# scale-slave.net
KiCad netlist of a schematic drawn in EAGLE
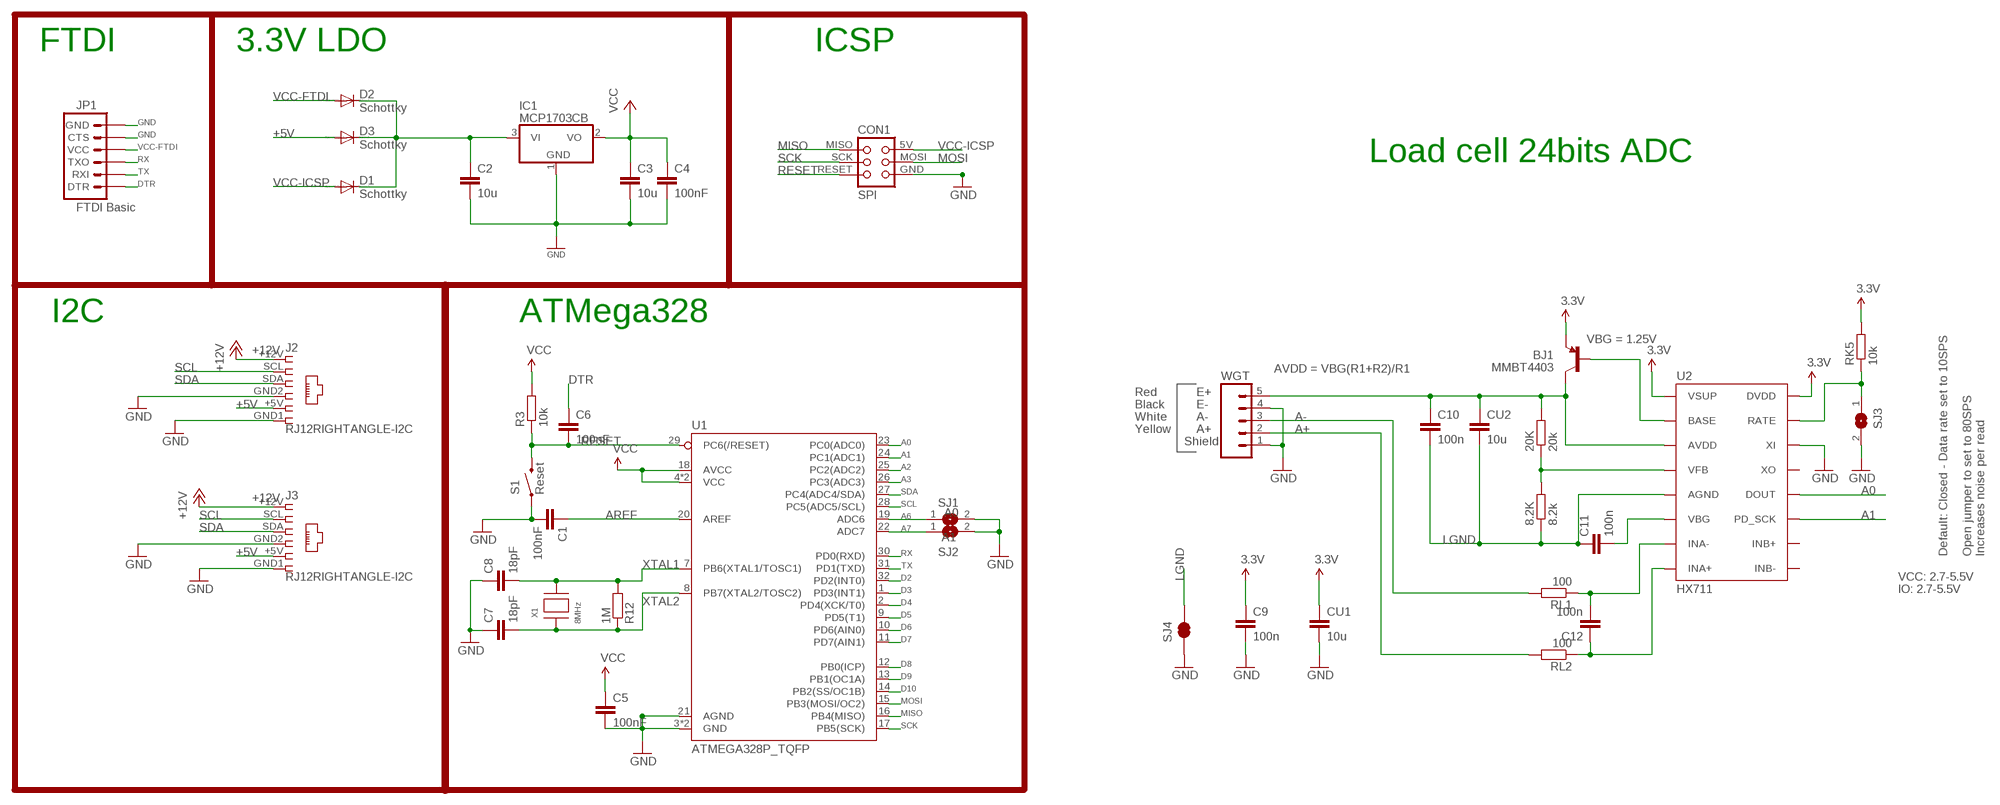
[diagram p0: schematic, sheet 1]

(export (version "E")
  (design (tool "Eeschema 10.0.6"))
  (components
    (comp (ref "8.2K")
      (value "8.2k")
      (footprint "eagle-import:M0805")
      (libsource (lib "eagle-import") (part "resistor_R-EU_M0805"))
    )
    (comp (ref "20K")
      (value "20k")
      (footprint "eagle-import:M0805")
      (libsource (lib "eagle-import") (part "resistor_R-EU_M0805"))
    )
    (comp (ref "BJ1")
      (value "MMBT4403")
      (footprint "eagle-import:SOT23-3")
      (libsource (lib "eagle-import") (part "TRANSISTOR_PNPMMBT4403"))
    )
    (comp (ref "C1")
      (value "100nF")
      (footprint "eagle-import:C0805K")
      (fields (field (name "MPN") "80-C1206C104K5R"))
      (libsource (lib "eagle-import") (part "rcl_334_C-EUC0805K"))
    )
    (comp (ref "C2")
      (value "10u")
      (footprint "eagle-import:C0805K")
      (fields (field (name "MPN") "77-VJ1206V106ZXQTBC"))
      (libsource (lib "eagle-import") (part "rcl_334_C-EUC0805K"))
    )
    (comp (ref "C3")
      (value "10u")
      (footprint "eagle-import:C0805K")
      (fields (field (name "MPN") "77-VJ1206V106ZXQTBC"))
      (libsource (lib "eagle-import") (part "rcl_334_C-EUC0805K"))
    )
    (comp (ref "C4")
      (value "100nF")
      (footprint "eagle-import:C0805K")
      (fields (field (name "MPN") "80-C1206C104K5R"))
      (libsource (lib "eagle-import") (part "rcl_334_C-EUC0805K"))
    )
    (comp (ref "C5")
      (value "100nF")
      (footprint "eagle-import:C0805K")
      (fields (field (name "MPN") "80-C1206C104K5R"))
      (libsource (lib "eagle-import") (part "rcl_334_C-EUC0805K"))
    )
    (comp (ref "C6")
      (value "100nF")
      (footprint "eagle-import:C0805K")
      (fields (field (name "MPN") "80-C1206C104K5R"))
      (libsource (lib "eagle-import") (part "rcl_334_C-EUC0805K"))
    )
    (comp (ref "C7")
      (value "18pF")
      (footprint "eagle-import:C0805K")
      (fields (field (name "MPN") "77-VJ1206A180JXXPBC"))
      (libsource (lib "eagle-import") (part "rcl_334_C-EUC0805K"))
    )
    (comp (ref "C8")
      (value "18pF")
      (footprint "eagle-import:C0805K")
      (fields (field (name "MPN") "77-VJ1206A180JXXPBC"))
      (libsource (lib "eagle-import") (part "rcl_334_C-EUC0805K"))
    )
    (comp (ref "C9")
      (value "100n")
      (footprint "eagle-import:C0805")
      (libsource (lib "eagle-import") (part "C-EUC0805"))
    )
    (comp (ref "C10")
      (value "100n")
      (footprint "eagle-import:C0805")
      (libsource (lib "eagle-import") (part "C-EUC0805"))
    )
    (comp (ref "C11")
      (value "100n")
      (footprint "eagle-import:C0805")
      (libsource (lib "eagle-import") (part "C-EUC0805"))
    )
    (comp (ref "C12")
      (value "100n")
      (footprint "eagle-import:C0805")
      (libsource (lib "eagle-import") (part "C-EUC0805"))
    )
    (comp (ref "CON1")
      (value "SPI")
      (footprint "eagle-import:TC2030-MCP")
      (libsource (lib "eagle-import") (part "TINYISPTAG"))
    )
    (comp (ref "CU1")
      (value "10u")
      (footprint "eagle-import:C0805")
      (libsource (lib "eagle-import") (part "C-EUC0805"))
    )
    (comp (ref "CU2")
      (value "10u")
      (footprint "eagle-import:C0805")
      (libsource (lib "eagle-import") (part "C-EUC0805"))
    )
    (comp (ref "D1")
      (value "Schottky")
      (footprint "eagle-import:SOD123")
      (fields (field (name "MPN") "621-1N5819HW-F"))
      (libsource (lib "eagle-import") (part "MBR0520LT"))
    )
    (comp (ref "D2")
      (value "Schottky")
      (footprint "eagle-import:SOD123")
      (fields (field (name "MPN") "621-1N5819HW-F"))
      (libsource (lib "eagle-import") (part "MBR0520LT"))
    )
    (comp (ref "D3")
      (value "Schottky")
      (footprint "eagle-import:SOD123")
      (fields (field (name "MPN") "621-1N5819HW-F"))
      (libsource (lib "eagle-import") (part "MBR0520LT"))
    )
    (comp (ref "IC1")
      (value "MCP1703CB")
      (footprint "eagle-import:SOT23")
      (libsource (lib "eagle-import") (part "MCP1703CB"))
    )
    (comp (ref "J2")
      (value "RJ12RIGHTANGLE-I2C")
      (footprint "eagle-import:RJ12-RIGHTANGLE-I2C")
      (libsource (lib "eagle-import") (part "RJ12RIGHTANGLE-I2C"))
    )
    (comp (ref "J3")
      (value "RJ12RIGHTANGLE-I2C")
      (footprint "eagle-import:RJ12-RIGHTANGLE-I2C")
      (libsource (lib "eagle-import") (part "RJ12RIGHTANGLE-I2C"))
    )
    (comp (ref "JP1")
      (value "FTDI Basic")
      (footprint "eagle-import:1X06")
      (libsource (lib "eagle-import") (part "ARDUINO_SERIAL_PROGRAMPTH"))
    )
    (comp (ref "R3")
      (value "10k")
      (footprint "eagle-import:R0805")
      (libsource (lib "eagle-import") (part "R-EU_R0805"))
    )
    (comp (ref "R12")
      (value "1M")
      (footprint "eagle-import:R0805")
      (libsource (lib "eagle-import") (part "R-EU_R0805"))
    )
    (comp (ref "RK5")
      (value "10k")
      (footprint "eagle-import:M0805")
      (libsource (lib "eagle-import") (part "resistor_R-EU_M0805"))
    )
    (comp (ref "RL1")
      (value "100")
      (footprint "eagle-import:M0805")
      (libsource (lib "eagle-import") (part "resistor_R-EU_M0805"))
    )
    (comp (ref "RL2")
      (value "100")
      (footprint "eagle-import:M0805")
      (libsource (lib "eagle-import") (part "resistor_R-EU_M0805"))
    )
    (comp (ref "S1")
      (value "Reset")
      (footprint "eagle-import:TACTILE-SWITCH-SMD-ALT01")
      (libsource (lib "eagle-import") (part "SWITCH-MOMENTARY-2SMD-ALT01"))
    )
    (comp (ref "SJ1")
      (value "A0")
      (footprint "eagle-import:SJ")
      (libsource (lib "eagle-import") (part "jumper_252_SJ"))
    )
    (comp (ref "SJ2")
      (value "A1")
      (footprint "eagle-import:SJ")
      (libsource (lib "eagle-import") (part "jumper_252_SJ"))
    )
    (comp (ref "SJ3") (value "SJ") (footprint "eagle-import:SJ") (libsource (lib "eagle-import") (part "SJ")))
    (comp (ref "SJ4")
      (value "JUMPER-PAD-2-NC_BY_TRACE")
      (footprint "eagle-import:PAD-JUMPER-2-NC_BY_TRACE_YES_SILK")
      (libsource (lib "eagle-import") (part "JUMPER-PAD-2-NC_BY_TRACE"))
    )
    (comp (ref "U1")
      (value "ATMEGA328P_TQFP")
      (footprint "eagle-import:TQFP32-08")
      (libsource (lib "eagle-import") (part "ATMEGA328P_TQFP"))
    )
    (comp (ref "U2")
      (value "HX711")
      (footprint "eagle-import:SO16")
      (libsource (lib "eagle-import") (part "HX711HX711"))
    )
    (comp (ref "WGT")
      (value "M05PTH")
      (footprint "eagle-import:1X05")
      (libsource (lib "eagle-import") (part "M05PTH"))
    )
    (comp (ref "X1")
      (value "8MHz")
      (footprint "eagle-import:NX6035")
      (fields (field (name "MPN") "729-F60800010"))
      (libsource (lib "eagle-import") (part "XTALNX6035"))
    )
  )
  (nets
    (net (code "1") (name "+12V") (class "Default")
      (node (ref "J2") (pin "+12V") (pinfunction "1_+12V") (pintype "bidirectional"))
      (node (ref "J3") (pin "+12V") (pinfunction "1_+12V") (pintype "bidirectional"))
    )
    (net (code "2") (name "/+5V") (class "Default")
      (node (ref "D3") (pin "A") (pinfunction "A_A") (pintype "passive"))
      (node (ref "J2") (pin "+5V") (pinfunction "5_+5V") (pintype "bidirectional"))
      (node (ref "J3") (pin "+5V") (pinfunction "5_+5V") (pintype "bidirectional"))
    )
    (net (code "3") (name "/A+") (class "Default")
      (node (ref "RL2") (pin "2") (pinfunction "2_2") (pintype "passive"))
      (node (ref "WGT") (pin "2") (pinfunction "2_2") (pintype "passive"))
    )
    (net (code "4") (name "/A-") (class "Default")
      (node (ref "RL1") (pin "2") (pinfunction "2_2") (pintype "passive"))
      (node (ref "WGT") (pin "3") (pinfunction "3_3") (pintype "passive"))
    )
    (net (code "5") (name "/A0") (class "Default")
      (node (ref "U1") (pin "23") (pinfunction "PC0(ADC0)_23") (pintype "bidirectional"))
      (node (ref "U2") (pin "12") (pinfunction "DOUT_12") (pintype "bidirectional"))
    )
    (net (code "6") (name "/A1") (class "Default")
      (node (ref "U1") (pin "24") (pinfunction "PC1(ADC1)_24") (pintype "bidirectional"))
      (node (ref "U2") (pin "11") (pinfunction "PD_SCK_11") (pintype "bidirectional"))
    )
    (net (code "7") (name "/A2") (class "Default")
      (node (ref "U1") (pin "25") (pinfunction "PC2(ADC2)_25") (pintype "bidirectional"))
    )
    (net (code "8") (name "/A3") (class "Default")
      (node (ref "U1") (pin "26") (pinfunction "PC3(ADC3)_26") (pintype "bidirectional"))
    )
    (net (code "9") (name "/A6") (class "Default")
      (node (ref "SJ1") (pin "1") (pinfunction "1_1") (pintype "passive"))
      (node (ref "U1") (pin "19") (pinfunction "ADC6_19") (pintype "bidirectional"))
    )
    (net (code "10") (name "/A7") (class "Default")
      (node (ref "SJ2") (pin "1") (pinfunction "1_1") (pintype "passive"))
      (node (ref "U1") (pin "22") (pinfunction "ADC7_22") (pintype "bidirectional"))
    )
    (net (code "11") (name "/AREF") (class "Default")
      (node (ref "C1") (pin "1") (pinfunction "1_1") (pintype "passive"))
      (node (ref "U1") (pin "20") (pinfunction "AREF_20") (pintype "bidirectional"))
    )
    (net (code "12") (name "/D2") (class "Default")
      (node (ref "U1") (pin "32") (pinfunction "PD2(INT0)_32") (pintype "bidirectional"))
    )
    (net (code "13") (name "/D3") (class "Default")
      (node (ref "U1") (pin "1") (pinfunction "PD3(INT1)_1") (pintype "bidirectional"))
    )
    (net (code "14") (name "/D4") (class "Default")
      (node (ref "U1") (pin "2") (pinfunction "PD4(XCK/T0)_2") (pintype "bidirectional"))
    )
    (net (code "15") (name "/D5") (class "Default")
      (node (ref "U1") (pin "9") (pinfunction "PD5(T1)_9") (pintype "bidirectional"))
    )
    (net (code "16") (name "/D6") (class "Default")
      (node (ref "U1") (pin "10") (pinfunction "PD6(AIN0)_10") (pintype "bidirectional"))
    )
    (net (code "17") (name "/D7") (class "Default")
      (node (ref "U1") (pin "11") (pinfunction "PD7(AIN1)_11") (pintype "bidirectional"))
    )
    (net (code "18") (name "/D8") (class "Default")
      (node (ref "U1") (pin "12") (pinfunction "PB0(ICP)_12") (pintype "bidirectional"))
    )
    (net (code "19") (name "/D9") (class "Default")
      (node (ref "U1") (pin "13") (pinfunction "PB1(OC1A)_13") (pintype "bidirectional"))
    )
    (net (code "20") (name "/D10") (class "Default")
      (node (ref "U1") (pin "14") (pinfunction "PB2(SS/OC1B)_14") (pintype "bidirectional"))
    )
    (net (code "21") (name "/DTR") (class "Default")
      (node (ref "C6") (pin "1") (pinfunction "1_1") (pintype "passive"))
      (node (ref "JP1") (pin "1") (pinfunction "DTR_1") (pintype "passive"))
    )
    (net (code "22") (name "/LGND") (class "Default")
      (node (ref "8.2K") (pin "1") (pinfunction "1_1") (pintype "passive"))
      (node (ref "C10") (pin "2") (pinfunction "2_2") (pintype "passive"))
      (node (ref "C11") (pin "1") (pinfunction "1_1") (pintype "passive"))
      (node (ref "CU2") (pin "2") (pinfunction "2_2") (pintype "passive"))
      (node (ref "SJ4") (pin "2") (pinfunction "2_2") (pintype "passive"))
      (node (ref "U2") (pin "5") (pinfunction "AGND_5") (pintype "bidirectional"))
    )
    (net (code "23") (name "/MISO") (class "Default")
      (node (ref "CON1") (pin "MISO") (pinfunction "MISO_MISO") (pintype "passive"))
      (node (ref "U1") (pin "16") (pinfunction "PB4(MISO)_16") (pintype "bidirectional"))
    )
    (net (code "24") (name "/MOSI") (class "Default")
      (node (ref "CON1") (pin "MOSI") (pinfunction "MOSI_MOSI") (pintype "passive"))
      (node (ref "U1") (pin "15") (pinfunction "PB3(MOSI/OC2)_15") (pintype "bidirectional"))
    )
    (net (code "25") (name "/RESET") (class "Default")
      (node (ref "C6") (pin "2") (pinfunction "2_2") (pintype "passive"))
      (node (ref "CON1") (pin "RESET") (pinfunction "RESET_RESET") (pintype "passive"))
      (node (ref "R3") (pin "1") (pinfunction "1_1") (pintype "passive"))
      (node (ref "S1") (pin "3") (pinfunction "2_3") (pintype "passive"))
      (node (ref "S1") (pin "4") (pinfunction "2_4") (pintype "passive"))
      (node (ref "U1") (pin "29") (pinfunction "PC6(/RESET)_29") (pintype "bidirectional"))
    )
    (net (code "26") (name "/RX") (class "Default")
      (node (ref "JP1") (pin "3") (pinfunction "TXO_3") (pintype "passive"))
      (node (ref "U1") (pin "30") (pinfunction "PD0(RXD)_30") (pintype "bidirectional"))
    )
    (net (code "27") (name "/SCK") (class "Default")
      (node (ref "CON1") (pin "SCK") (pinfunction "SCK_SCK") (pintype "passive"))
      (node (ref "U1") (pin "17") (pinfunction "PB5(SCK)_17") (pintype "bidirectional"))
    )
    (net (code "28") (name "/SCL") (class "Default")
      (node (ref "J2") (pin "SCL") (pinfunction "2_SCL") (pintype "bidirectional"))
      (node (ref "J3") (pin "SCL") (pinfunction "2_SCL") (pintype "bidirectional"))
      (node (ref "U1") (pin "28") (pinfunction "PC5(ADC5/SCL)_28") (pintype "bidirectional"))
    )
    (net (code "29") (name "/SDA") (class "Default")
      (node (ref "J2") (pin "SDA") (pinfunction "3_SDA") (pintype "bidirectional"))
      (node (ref "J3") (pin "SDA") (pinfunction "3_SDA") (pintype "bidirectional"))
      (node (ref "U1") (pin "27") (pinfunction "PC4(ADC4/SDA)_27") (pintype "bidirectional"))
    )
    (net (code "30") (name "/TX") (class "Default")
      (node (ref "JP1") (pin "2") (pinfunction "RXI_2") (pintype "passive"))
      (node (ref "U1") (pin "31") (pinfunction "PD1(TXD)_31") (pintype "bidirectional"))
    )
    (net (code "31") (name "/VCC-FTDI") (class "Default")
      (node (ref "D2") (pin "A") (pinfunction "A_A") (pintype "passive"))
      (node (ref "JP1") (pin "4") (pinfunction "VCC_4") (pintype "passive"))
    )
    (net (code "32") (name "/VCC-ICSP") (class "Default")
      (node (ref "CON1") (pin "5V") (pinfunction "VCC_5V") (pintype "passive"))
      (node (ref "D1") (pin "A") (pinfunction "A_A") (pintype "passive"))
    )
    (net (code "33") (name "/XTAL1") (class "Default")
      (node (ref "C8") (pin "2") (pinfunction "2_2") (pintype "passive"))
      (node (ref "R12") (pin "2") (pinfunction "2_2") (pintype "passive"))
      (node (ref "U1") (pin "7") (pinfunction "PB6(XTAL1/TOSC1)_7") (pintype "bidirectional"))
      (node (ref "X1") (pin "P$2") (pinfunction "P$2_P$2") (pintype "bidirectional"))
    )
    (net (code "34") (name "/XTAL2") (class "Default")
      (node (ref "C7") (pin "2") (pinfunction "2_2") (pintype "passive"))
      (node (ref "R12") (pin "1") (pinfunction "1_1") (pintype "passive"))
      (node (ref "U1") (pin "8") (pinfunction "PB7(XTAL2/TOSC2)_8") (pintype "bidirectional"))
      (node (ref "X1") (pin "P$1") (pinfunction "P$1_P$1") (pintype "bidirectional"))
    )
    (net (code "35") (name "3.3V") (class "Default")
      (node (ref "BJ1") (pin "2") (pinfunction "E_2") (pintype "passive"))
      (node (ref "C9") (pin "1") (pinfunction "1_1") (pintype "passive"))
      (node (ref "CU1") (pin "1") (pinfunction "1_1") (pintype "passive"))
      (node (ref "RK5") (pin "2") (pinfunction "2_2") (pintype "passive"))
      (node (ref "U2") (pin "1") (pinfunction "VSUP_1") (pintype "bidirectional"))
      (node (ref "U2") (pin "16") (pinfunction "DVDD_16") (pintype "bidirectional"))
    )
    (net (code "36") (name "GND") (class "Default")
      (node (ref "C1") (pin "2") (pinfunction "2_2") (pintype "passive"))
      (node (ref "C2") (pin "2") (pinfunction "2_2") (pintype "passive"))
      (node (ref "C3") (pin "2") (pinfunction "2_2") (pintype "passive"))
      (node (ref "C4") (pin "2") (pinfunction "2_2") (pintype "passive"))
      (node (ref "C5") (pin "2") (pinfunction "2_2") (pintype "passive"))
      (node (ref "C7") (pin "1") (pinfunction "1_1") (pintype "passive"))
      (node (ref "C8") (pin "1") (pinfunction "1_1") (pintype "passive"))
      (node (ref "C9") (pin "2") (pinfunction "2_2") (pintype "passive"))
      (node (ref "CON1") (pin "GND") (pinfunction "GND_GND") (pintype "passive"))
      (node (ref "CU1") (pin "2") (pinfunction "2_2") (pintype "passive"))
      (node (ref "IC1") (pin "1") (pinfunction "GND_1") (pintype "passive"))
      (node (ref "J2") (pin "GND1") (pinfunction "6_GND1") (pintype "bidirectional"))
      (node (ref "J2") (pin "GND2") (pinfunction "4_GND2") (pintype "bidirectional"))
      (node (ref "J3") (pin "GND1") (pinfunction "6_GND1") (pintype "bidirectional"))
      (node (ref "J3") (pin "GND2") (pinfunction "4_GND2") (pintype "bidirectional"))
      (node (ref "JP1") (pin "5") (pinfunction "CTS_5") (pintype "passive"))
      (node (ref "JP1") (pin "6") (pinfunction "GND_6") (pintype "passive"))
      (node (ref "S1") (pin "1") (pinfunction "1_1") (pintype "passive"))
      (node (ref "S1") (pin "2") (pinfunction "1_2") (pintype "passive"))
      (node (ref "SJ1") (pin "2") (pinfunction "2_2") (pintype "passive"))
      (node (ref "SJ2") (pin "2") (pinfunction "2_2") (pintype "passive"))
      (node (ref "SJ3") (pin "2") (pinfunction "2_2") (pintype "passive"))
      (node (ref "SJ4") (pin "1") (pinfunction "1_1") (pintype "passive"))
      (node (ref "U1") (pin "21") (pinfunction "AGND_21") (pintype "bidirectional"))
      (node (ref "U1") (pin "3") (pinfunction "GND_3") (pintype "bidirectional"))
      (node (ref "U1") (pin "5") (pinfunction "GND_5") (pintype "bidirectional"))
      (node (ref "U2") (pin "14") (pinfunction "XI_14") (pintype "bidirectional"))
      (node (ref "WGT") (pin "1") (pinfunction "1_1") (pintype "passive"))
      (node (ref "WGT") (pin "4") (pinfunction "4_4") (pintype "passive"))
    )
    (net (code "37") (name "Net-(BJ1-B)") (class "Default")
      (node (ref "BJ1") (pin "1") (pinfunction "B_1") (pintype "passive"))
      (node (ref "U2") (pin "2") (pinfunction "BASE_2") (pintype "bidirectional"))
    )
    (net (code "38") (name "Net-(BJ1-C)") (class "Default")
      (node (ref "20K") (pin "2") (pinfunction "2_2") (pintype "passive"))
      (node (ref "BJ1") (pin "3") (pinfunction "C_3") (pintype "passive"))
      (node (ref "C10") (pin "1") (pinfunction "1_1") (pintype "passive"))
      (node (ref "CU2") (pin "1") (pinfunction "1_1") (pintype "passive"))
      (node (ref "U2") (pin "3") (pinfunction "AVDD_3") (pintype "bidirectional"))
      (node (ref "WGT") (pin "5") (pinfunction "5_5") (pintype "passive"))
    )
    (net (code "39") (name "Net-(IC1-VI)") (class "Default")
      (node (ref "C2") (pin "1") (pinfunction "1_1") (pintype "passive"))
      (node (ref "D1") (pin "C") (pinfunction "C_C") (pintype "passive"))
      (node (ref "D2") (pin "C") (pinfunction "C_C") (pintype "passive"))
      (node (ref "D3") (pin "C") (pinfunction "C_C") (pintype "passive"))
      (node (ref "IC1") (pin "3") (pinfunction "VI_3") (pintype "input"))
    )
    (net (code "40") (name "Net-(U2-INA+)") (class "Default")
      (node (ref "C12") (pin "1") (pinfunction "1_1") (pintype "passive"))
      (node (ref "RL2") (pin "1") (pinfunction "1_1") (pintype "passive"))
      (node (ref "U2") (pin "8") (pinfunction "INA+_8") (pintype "bidirectional"))
    )
    (net (code "41") (name "Net-(U2-INA-)") (class "Default")
      (node (ref "C12") (pin "2") (pinfunction "2_2") (pintype "passive"))
      (node (ref "RL1") (pin "1") (pinfunction "1_1") (pintype "passive"))
      (node (ref "U2") (pin "7") (pinfunction "INA-_7") (pintype "bidirectional"))
    )
    (net (code "42") (name "Net-(U2-RATE)") (class "Default")
      (node (ref "RK5") (pin "1") (pinfunction "1_1") (pintype "passive"))
      (node (ref "SJ3") (pin "1") (pinfunction "1_1") (pintype "passive"))
      (node (ref "U2") (pin "15") (pinfunction "RATE_15") (pintype "bidirectional"))
    )
    (net (code "43") (name "Net-(U2-VBG)") (class "Default")
      (node (ref "C11") (pin "2") (pinfunction "2_2") (pintype "passive"))
      (node (ref "U2") (pin "6") (pinfunction "VBG_6") (pintype "bidirectional"))
    )
    (net (code "44") (name "Net-(U2-VFB)") (class "Default")
      (node (ref "20K") (pin "1") (pinfunction "1_1") (pintype "passive"))
      (node (ref "8.2K") (pin "2") (pinfunction "2_2") (pintype "passive"))
      (node (ref "U2") (pin "4") (pinfunction "VFB_4") (pintype "bidirectional"))
    )
    (net (code "45") (name "VCC") (class "Default")
      (node (ref "C3") (pin "1") (pinfunction "1_1") (pintype "passive"))
      (node (ref "C4") (pin "1") (pinfunction "1_1") (pintype "passive"))
      (node (ref "C5") (pin "1") (pinfunction "1_1") (pintype "passive"))
      (node (ref "IC1") (pin "2") (pinfunction "VO_2") (pintype "passive"))
      (node (ref "R3") (pin "2") (pinfunction "2_2") (pintype "passive"))
      (node (ref "U1") (pin "18") (pinfunction "AVCC_18") (pintype "bidirectional"))
      (node (ref "U1") (pin "4") (pinfunction "VCC_4") (pintype "bidirectional"))
      (node (ref "U1") (pin "6") (pinfunction "VCC_6") (pintype "bidirectional"))
    )
    (net (code "46") (name "unconnected-(U2-INB+-Pad10)") (class "Default")
      (node (ref "U2") (pin "10") (pinfunction "INB+_10") (pintype "bidirectional"))
    )
    (net (code "47") (name "unconnected-(U2-INB--Pad9)") (class "Default")
      (node (ref "U2") (pin "9") (pinfunction "INB-_9") (pintype "bidirectional"))
    )
    (net (code "48") (name "unconnected-(U2-XO-Pad13)") (class "Default")
      (node (ref "U2") (pin "13") (pinfunction "XO_13") (pintype "bidirectional"))
    )
  )
)
